# USBConnectors_v1.net
KiCad netlist of a schematic drawn in EAGLE
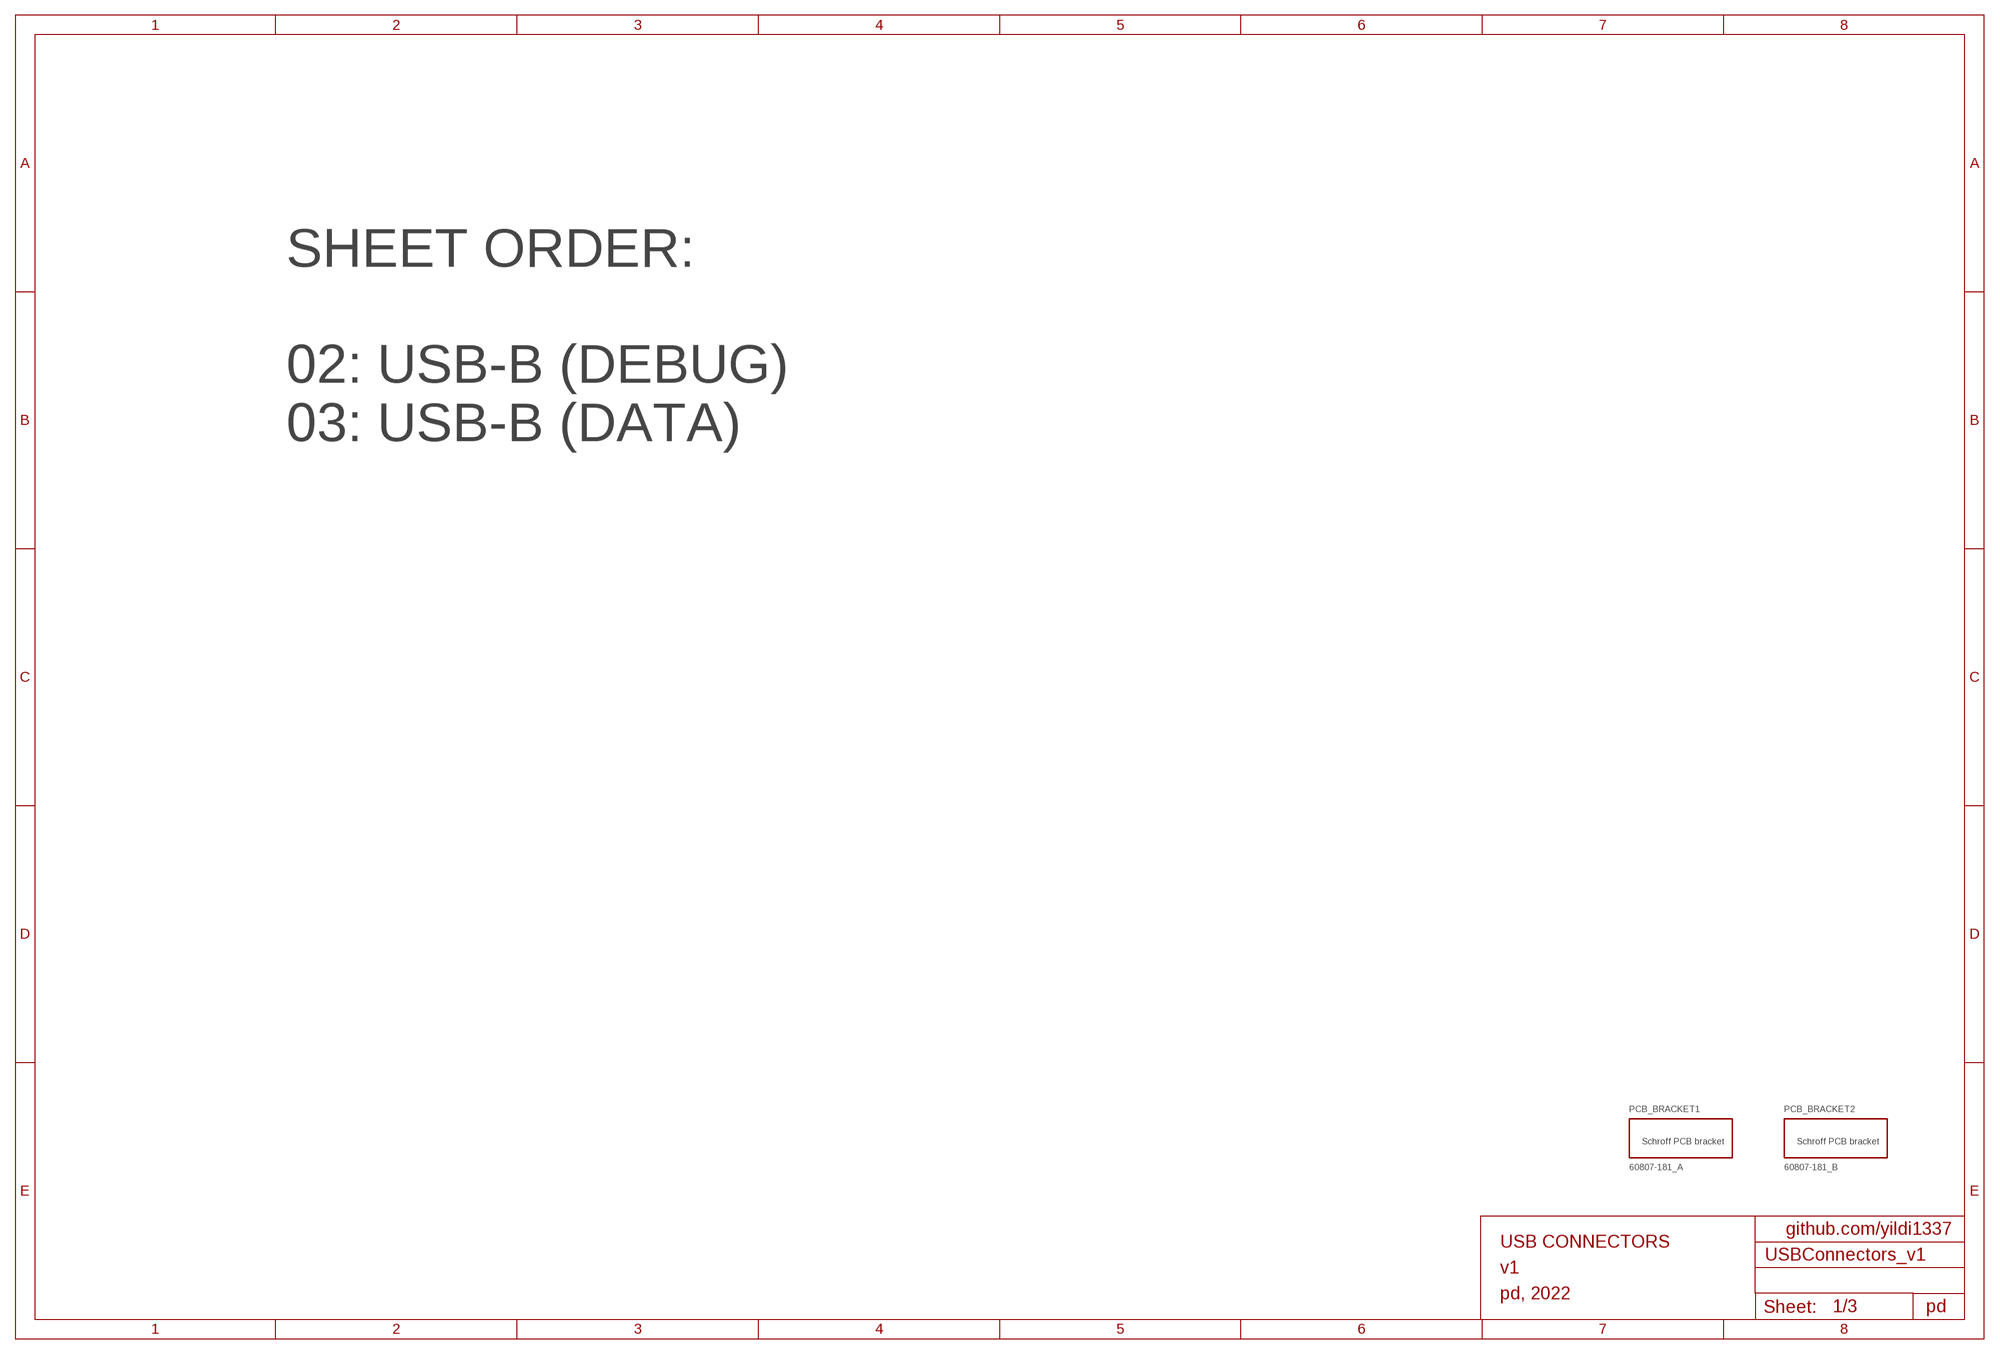
[diagram p0: schematic, sheet 1]
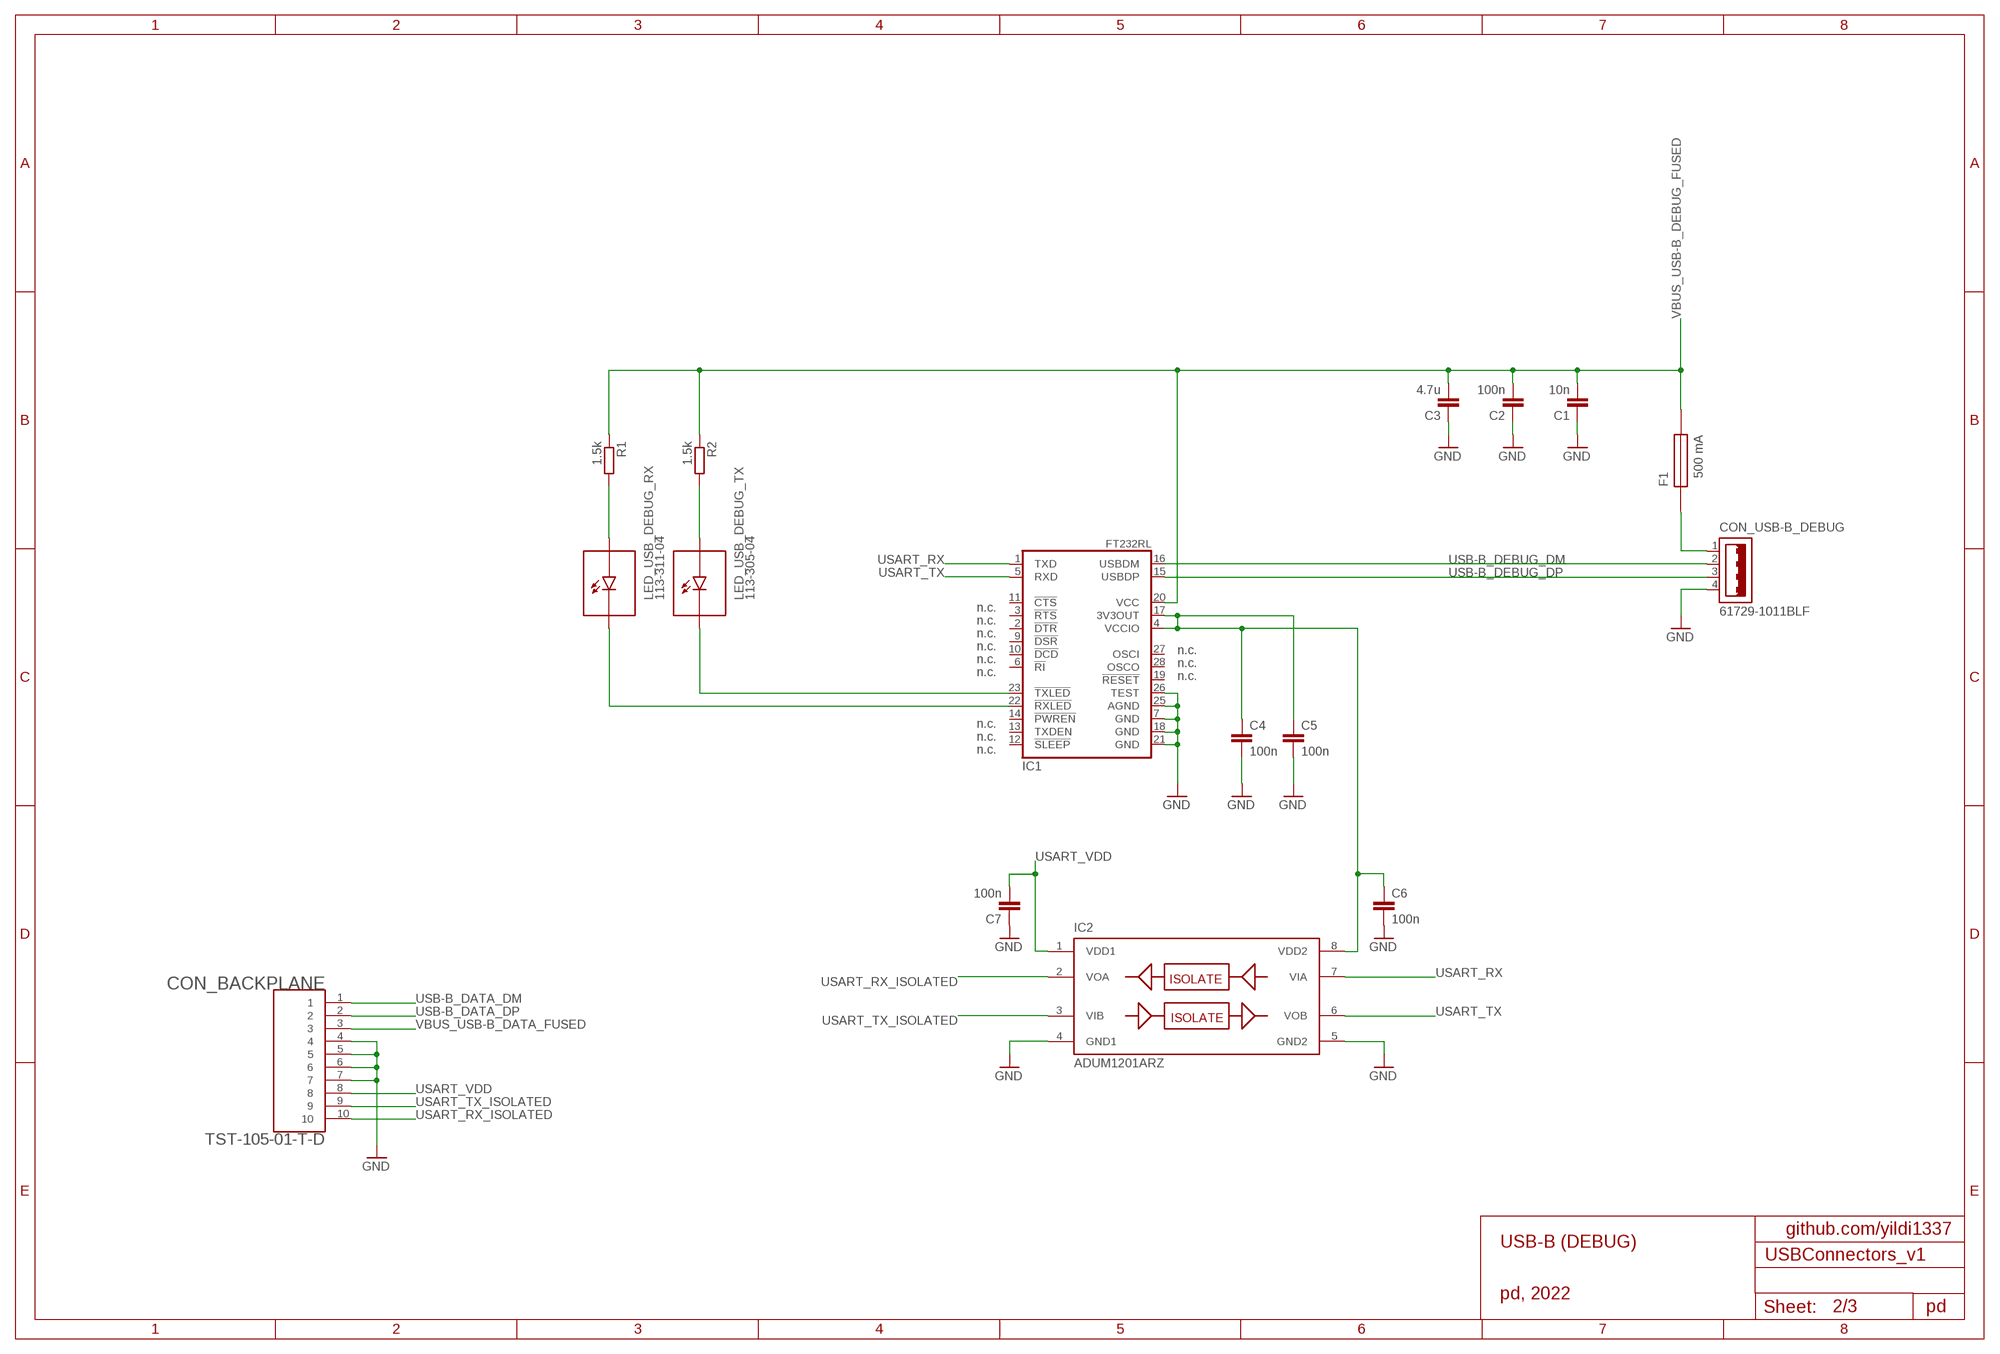
[diagram p1: schematic, sheet 2]
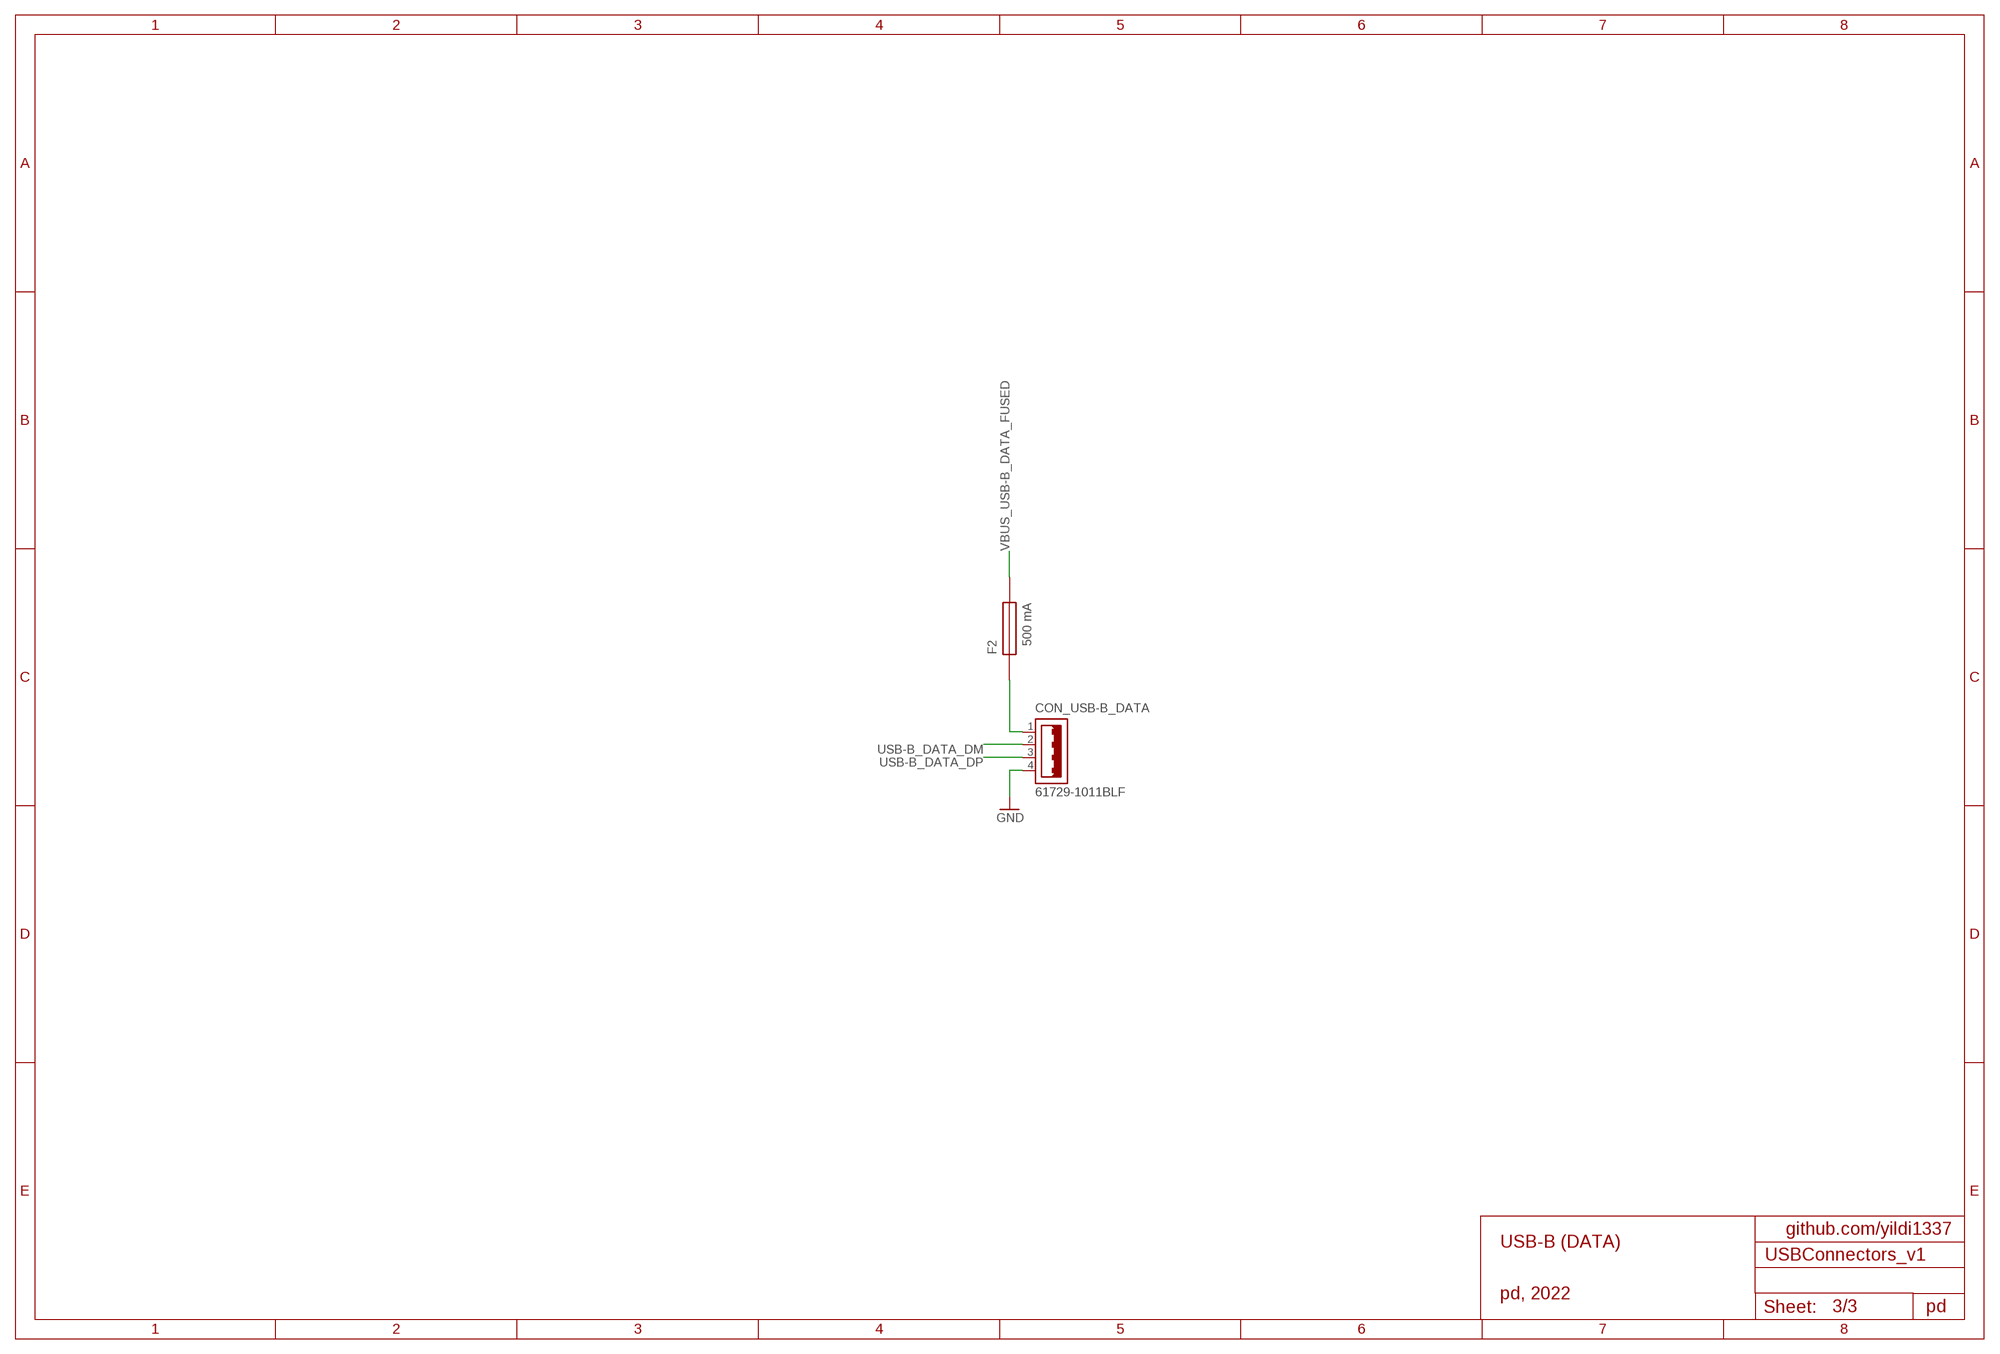
[diagram p2: schematic, sheet 3]

(export (version "E")
  (design (tool "Eeschema 10.0.6"))
  (components
    (comp (ref "C1")
      (value "10n")
      (footprint "eagle-import:C0603")
      (libsource (lib "eagle-import") (part "C-EUC0603"))
    )
    (comp (ref "C2")
      (value "100n")
      (footprint "eagle-import:C0603")
      (libsource (lib "eagle-import") (part "C-EUC0603"))
    )
    (comp (ref "C3")
      (value "4.7u")
      (footprint "eagle-import:C0603")
      (libsource (lib "eagle-import") (part "C-EUC0603"))
    )
    (comp (ref "C4")
      (value "100n")
      (footprint "eagle-import:C0603")
      (libsource (lib "eagle-import") (part "C-EUC0603"))
    )
    (comp (ref "C5")
      (value "100n")
      (footprint "eagle-import:C0603")
      (libsource (lib "eagle-import") (part "C-EUC0603"))
    )
    (comp (ref "C6")
      (value "100n")
      (footprint "eagle-import:C0603")
      (libsource (lib "eagle-import") (part "C-EUC0603"))
    )
    (comp (ref "C7")
      (value "100n")
      (footprint "eagle-import:C0603")
      (libsource (lib "eagle-import") (part "C-EUC0603"))
    )
    (comp (ref "CON_BACKPLANE")
      (value "TST-105-01-T-D")
      (footprint "eagle-import:TST-105-01-T-D")
      (libsource (lib "eagle-import") (part "TST-105-01-T-D"))
    )
    (comp (ref "CON_USB-B_DEBUG")
      (value "61729-1011BLF")
      (footprint "eagle-import:61729-1011BLF")
      (libsource (lib "eagle-import") (part "61729-1011BLF"))
    )
    (comp (ref "F1")
      (value "500 mA")
      (footprint "eagle-import:LITTELFUSE_466_SERIES")
      (libsource (lib "eagle-import") (part "LITTELFUSE_466_SERIES"))
    )
    (comp (ref "IC1")
      (value "FT232RL")
      (footprint "eagle-import:FT232RL")
      (libsource (lib "eagle-import") (part "FT232RL"))
    )
    (comp (ref "IC2")
      (value "ADUM1201ARZ")
      (footprint "eagle-import:SO8")
      (libsource (lib "eagle-import") (part "ADUM1201"))
    )
    (comp (ref "LED_USB_DEBUG_RX")
      (value "113-311-04")
      (footprint "eagle-import:113-311-04")
      (libsource (lib "eagle-import") (part "113-311-04"))
    )
    (comp (ref "LED_USB_DEBUG_TX")
      (value "113-305-04")
      (footprint "eagle-import:113-305-04")
      (libsource (lib "eagle-import") (part "113-305-04"))
    )
    (comp (ref "R1")
      (value "1.5k")
      (footprint "eagle-import:R0603")
      (libsource (lib "eagle-import") (part "R-EU_R0603"))
    )
    (comp (ref "R2")
      (value "1.5k")
      (footprint "eagle-import:R0603")
      (libsource (lib "eagle-import") (part "R-EU_R0603"))
    )
    (comp (ref "CON_USB-B_DATA")
      (value "61729-1011BLF")
      (footprint "eagle-import:61729-1011BLF")
      (libsource (lib "eagle-import") (part "61729-1011BLF"))
    )
    (comp (ref "F2")
      (value "500 mA")
      (footprint "eagle-import:LITTELFUSE_466_SERIES")
      (libsource (lib "eagle-import") (part "LITTELFUSE_466_SERIES"))
    )
    (comp (ref "PCB_BRACKET1")
      (value "60807-181_A")
      (footprint "eagle-import:60807-181_A")
      (libsource (lib "eagle-import") (part "60807-181_A"))
    )
    (comp (ref "PCB_BRACKET2")
      (value "60807-181_B")
      (footprint "eagle-import:60807-181_B")
      (libsource (lib "eagle-import") (part "60807-181_B"))
    )
  )
  (nets
    (net (code "1") (name "GND") (class "Default")
      (node (ref "C1") (pin "2") (pinfunction "2_2") (pintype "passive"))
      (node (ref "C2") (pin "1") (pinfunction "1_1") (pintype "passive"))
      (node (ref "C3") (pin "1") (pinfunction "1_1") (pintype "passive"))
      (node (ref "C4") (pin "2") (pinfunction "2_2") (pintype "passive"))
      (node (ref "C5") (pin "2") (pinfunction "2_2") (pintype "passive"))
      (node (ref "C6") (pin "2") (pinfunction "2_2") (pintype "passive"))
      (node (ref "C7") (pin "1") (pinfunction "1_1") (pintype "passive"))
      (node (ref "CON_BACKPLANE") (pin "4") (pinfunction "4_4") (pintype "passive"))
      (node (ref "CON_BACKPLANE") (pin "5") (pinfunction "5_5") (pintype "passive"))
      (node (ref "CON_BACKPLANE") (pin "6") (pinfunction "6_6") (pintype "passive"))
      (node (ref "CON_BACKPLANE") (pin "7") (pinfunction "7_7") (pintype "passive"))
      (node (ref "CON_USB-B_DATA") (pin "4") (pinfunction "4_4") (pintype "passive"))
      (node (ref "CON_USB-B_DEBUG") (pin "4") (pinfunction "4_4") (pintype "passive"))
      (node (ref "IC1") (pin "18") (pinfunction "GND_18") (pintype "power_in"))
      (node (ref "IC1") (pin "21") (pinfunction "GND_21") (pintype "power_in"))
      (node (ref "IC1") (pin "25") (pinfunction "AGND_25") (pintype "power_in"))
      (node (ref "IC1") (pin "26") (pinfunction "TEST_26") (pintype "input"))
      (node (ref "IC1") (pin "7") (pinfunction "GND_7") (pintype "power_in"))
      (node (ref "IC2") (pin "4") (pinfunction "GND1_4") (pintype "bidirectional"))
      (node (ref "IC2") (pin "5") (pinfunction "GND2_5") (pintype "bidirectional"))
    )
    (net (code "2") (name "Net-(F1-P$1)") (class "Default")
      (node (ref "CON_USB-B_DEBUG") (pin "1") (pinfunction "1_1") (pintype "passive"))
      (node (ref "F1") (pin "1") (pinfunction "P$1_1") (pintype "bidirectional"))
    )
    (net (code "3") (name "Net-(F2-P$1)") (class "Default")
      (node (ref "CON_USB-B_DATA") (pin "1") (pinfunction "1_1") (pintype "passive"))
      (node (ref "F2") (pin "1") (pinfunction "P$1_1") (pintype "bidirectional"))
    )
    (net (code "4") (name "Net-(IC1-3V3OUT)") (class "Default")
      (node (ref "C4") (pin "1") (pinfunction "1_1") (pintype "passive"))
      (node (ref "C5") (pin "1") (pinfunction "1_1") (pintype "passive"))
      (node (ref "C6") (pin "1") (pinfunction "1_1") (pintype "passive"))
      (node (ref "IC1") (pin "17") (pinfunction "3V3OUT_17") (pintype "power_in"))
      (node (ref "IC1") (pin "4") (pinfunction "VCCIO_4") (pintype "power_in"))
      (node (ref "IC2") (pin "8") (pinfunction "VDD2_8") (pintype "bidirectional"))
    )
    (net (code "5") (name "Net-(IC1-~{RXLED})") (class "Default")
      (node (ref "IC1") (pin "22") (pinfunction "~{RXLED}_22") (pintype "input"))
      (node (ref "LED_USB_DEBUG_RX") (pin "-") (pinfunction "C_-") (pintype "passive"))
    )
    (net (code "6") (name "Net-(IC1-~{TXLED})") (class "Default")
      (node (ref "IC1") (pin "23") (pinfunction "~{TXLED}_23") (pintype "input"))
      (node (ref "LED_USB_DEBUG_TX") (pin "-") (pinfunction "C_-") (pintype "passive"))
    )
    (net (code "7") (name "Net-(LED_USB_DEBUG_RX-A)") (class "Default")
      (node (ref "LED_USB_DEBUG_RX") (pin "+") (pinfunction "A_+") (pintype "passive"))
      (node (ref "R1") (pin "2") (pinfunction "2_2") (pintype "passive"))
    )
    (net (code "8") (name "Net-(LED_USB_DEBUG_TX-A)") (class "Default")
      (node (ref "LED_USB_DEBUG_TX") (pin "+") (pinfunction "A_+") (pintype "passive"))
      (node (ref "R2") (pin "2") (pinfunction "2_2") (pintype "passive"))
    )
    (net (code "9") (name "USART_RX") (class "Default")
      (node (ref "IC1") (pin "1") (pinfunction "TXD_1") (pintype "output"))
      (node (ref "IC2") (pin "7") (pinfunction "VIA_7") (pintype "bidirectional"))
    )
    (net (code "10") (name "USART_RX_ISOLATED") (class "Default")
      (node (ref "CON_BACKPLANE") (pin "10") (pinfunction "10_10") (pintype "passive"))
      (node (ref "IC2") (pin "2") (pinfunction "VOA_2") (pintype "bidirectional"))
    )
    (net (code "11") (name "USART_TX") (class "Default")
      (node (ref "IC1") (pin "5") (pinfunction "RXD_5") (pintype "input"))
      (node (ref "IC2") (pin "6") (pinfunction "VOB_6") (pintype "bidirectional"))
    )
    (net (code "12") (name "USART_TX_ISOLATED") (class "Default")
      (node (ref "CON_BACKPLANE") (pin "9") (pinfunction "9_9") (pintype "passive"))
      (node (ref "IC2") (pin "3") (pinfunction "VIB_3") (pintype "bidirectional"))
    )
    (net (code "13") (name "USART_VDD") (class "Default")
      (node (ref "C7") (pin "2") (pinfunction "2_2") (pintype "passive"))
      (node (ref "CON_BACKPLANE") (pin "8") (pinfunction "8_8") (pintype "passive"))
      (node (ref "IC2") (pin "1") (pinfunction "VDD1_1") (pintype "bidirectional"))
    )
    (net (code "14") (name "USB-B_DATA_DM") (class "Default")
      (node (ref "CON_BACKPLANE") (pin "1") (pinfunction "1_1") (pintype "passive"))
      (node (ref "CON_USB-B_DATA") (pin "2") (pinfunction "2_2") (pintype "passive"))
    )
    (net (code "15") (name "USB-B_DATA_DP") (class "Default")
      (node (ref "CON_BACKPLANE") (pin "2") (pinfunction "2_2") (pintype "passive"))
      (node (ref "CON_USB-B_DATA") (pin "3") (pinfunction "3_3") (pintype "passive"))
    )
    (net (code "16") (name "USB-B_DEBUG_DM") (class "Default")
      (node (ref "CON_USB-B_DEBUG") (pin "2") (pinfunction "2_2") (pintype "passive"))
      (node (ref "IC1") (pin "16") (pinfunction "USBDM_16") (pintype "bidirectional"))
    )
    (net (code "17") (name "USB-B_DEBUG_DP") (class "Default")
      (node (ref "CON_USB-B_DEBUG") (pin "3") (pinfunction "3_3") (pintype "passive"))
      (node (ref "IC1") (pin "15") (pinfunction "USBDP_15") (pintype "bidirectional"))
    )
    (net (code "18") (name "VBUS_USB-B_DATA_FUSED") (class "Default")
      (node (ref "CON_BACKPLANE") (pin "3") (pinfunction "3_3") (pintype "passive"))
      (node (ref "F2") (pin "2") (pinfunction "P$2_2") (pintype "bidirectional"))
    )
    (net (code "19") (name "VBUS_USB-B_DEBUG_FUSED") (class "Default")
      (node (ref "C1") (pin "1") (pinfunction "1_1") (pintype "passive"))
      (node (ref "C2") (pin "2") (pinfunction "2_2") (pintype "passive"))
      (node (ref "C3") (pin "2") (pinfunction "2_2") (pintype "passive"))
      (node (ref "F1") (pin "2") (pinfunction "P$2_2") (pintype "bidirectional"))
      (node (ref "IC1") (pin "20") (pinfunction "VCC_20") (pintype "power_in"))
      (node (ref "R1") (pin "1") (pinfunction "1_1") (pintype "passive"))
      (node (ref "R2") (pin "1") (pinfunction "1_1") (pintype "passive"))
    )
    (net (code "20") (name "unconnected-(IC1-OSCI-Pad27)") (class "Default")
      (node (ref "IC1") (pin "27") (pinfunction "OSCI_27") (pintype "no_connect"))
    )
    (net (code "21") (name "unconnected-(IC1-OSCO-Pad28)") (class "Default")
      (node (ref "IC1") (pin "28") (pinfunction "OSCO_28") (pintype "output"))
    )
    (net (code "22") (name "unconnected-(IC1-TXDEN-Pad13)") (class "Default")
      (node (ref "IC1") (pin "13") (pinfunction "TXDEN_13") (pintype "no_connect"))
    )
    (net (code "23") (name "unconnected-(IC1-~{CTS}-Pad11)") (class "Default")
      (node (ref "IC1") (pin "11") (pinfunction "~{CTS}_11") (pintype "input"))
    )
    (net (code "24") (name "unconnected-(IC1-~{DCD}-Pad10)") (class "Default")
      (node (ref "IC1") (pin "10") (pinfunction "~{DCD}_10") (pintype "no_connect"))
    )
    (net (code "25") (name "unconnected-(IC1-~{DSR}-Pad9)") (class "Default")
      (node (ref "IC1") (pin "9") (pinfunction "~{DSR}_9") (pintype "no_connect"))
    )
    (net (code "26") (name "unconnected-(IC1-~{DTR}-Pad2)") (class "Default")
      (node (ref "IC1") (pin "2") (pinfunction "~{DTR}_2") (pintype "output"))
    )
    (net (code "27") (name "unconnected-(IC1-~{PWREN}-Pad14)") (class "Default")
      (node (ref "IC1") (pin "14") (pinfunction "~{PWREN}_14") (pintype "no_connect"))
    )
    (net (code "28") (name "unconnected-(IC1-~{RESET}-Pad19)") (class "Default")
      (node (ref "IC1") (pin "19") (pinfunction "~{RESET}_19") (pintype "no_connect"))
    )
    (net (code "29") (name "unconnected-(IC1-~{RI}-Pad6)") (class "Default")
      (node (ref "IC1") (pin "6") (pinfunction "~{RI}_6") (pintype "no_connect"))
    )
    (net (code "30") (name "unconnected-(IC1-~{RTS}-Pad3)") (class "Default")
      (node (ref "IC1") (pin "3") (pinfunction "~{RTS}_3") (pintype "output"))
    )
    (net (code "31") (name "unconnected-(IC1-~{SLEEP}-Pad12)") (class "Default")
      (node (ref "IC1") (pin "12") (pinfunction "~{SLEEP}_12") (pintype "no_connect"))
    )
  )
)
